# Basic_flex_IMU.net
KiCad netlist of a schematic drawn in Altium Designer
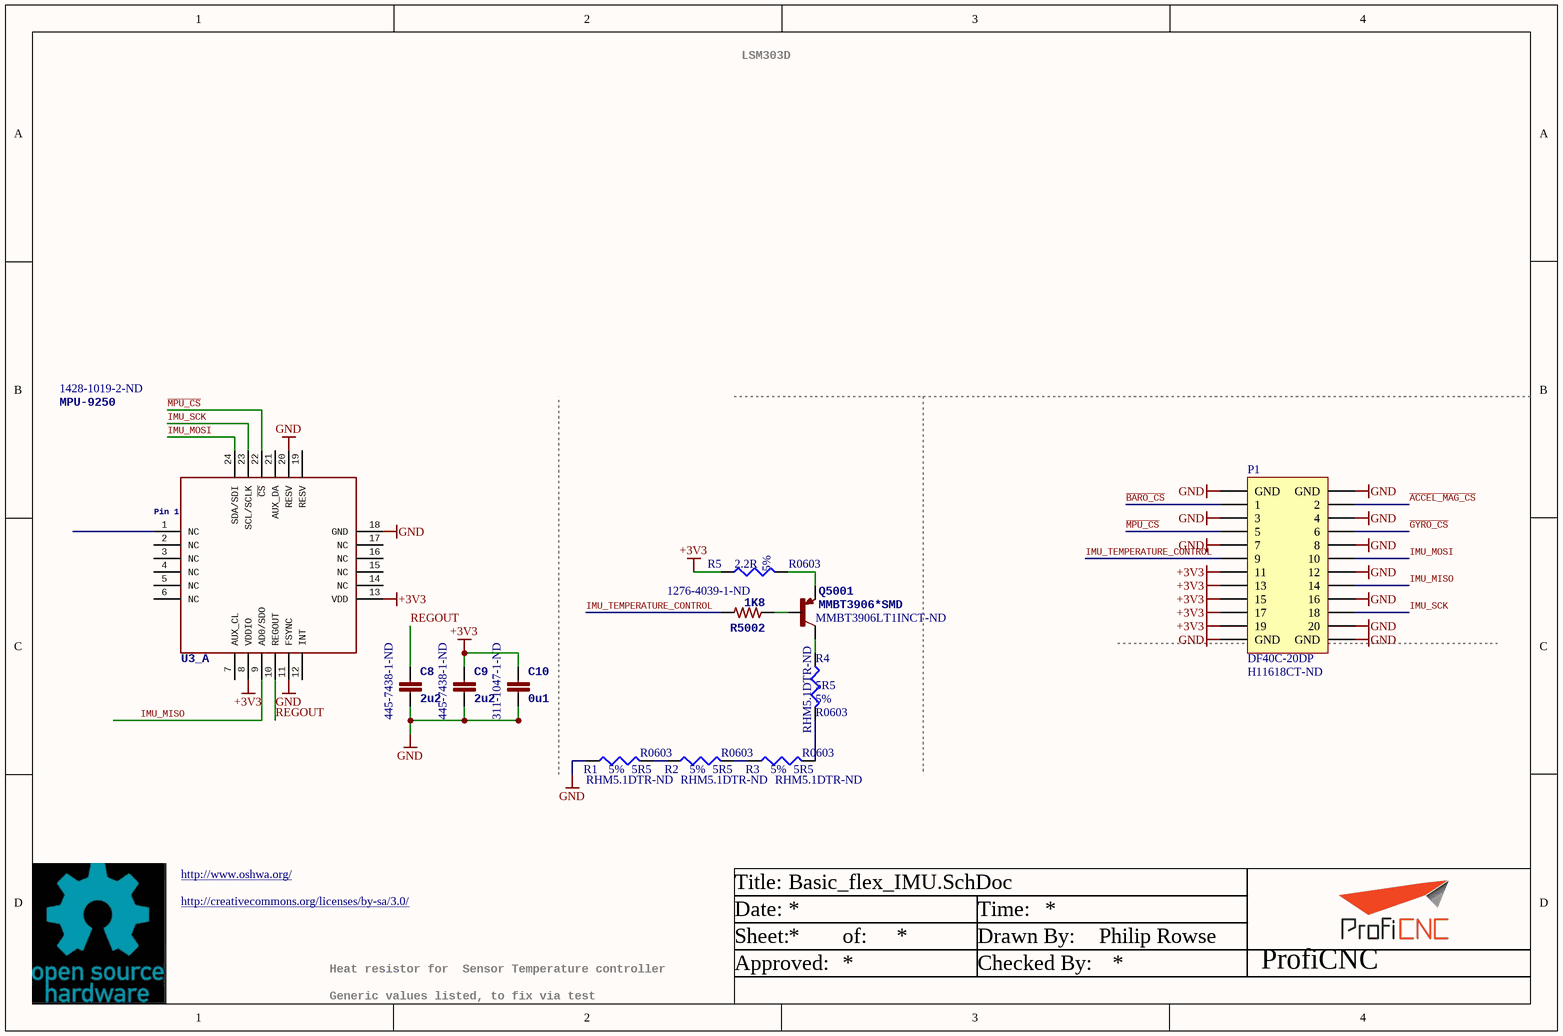
[diagram p0: Basic_flex_IMU.SchDoc]

(export (version "E")
  (design (tool "Eeschema 10.0.6"))
  (components
    (comp (ref "C8")
      (value "2u2")
      (footprint "0603-CAP")
      (description "Capacitor, 2.2uF, 16V, 10%, X6S, 0603, Ceramic")
      (fields
        (field (name "PARTNO") "C1608X6S1C225K080AC")
        (field (name "SUPPLIER PART NUMBER 1") "445-7438-1-ND")
        (field (name "3DR_PARTNO") "ECM0619")
      )
      (libsource (lib "lib_pixhawk") (part "CAPACITOR-0603"))
    )
    (comp (ref "C9")
      (value "2u2")
      (footprint "0603-CAP")
      (description "Capacitor, 2.2uF, 16V, 10%, X6S, 0603, Ceramic")
      (fields
        (field (name "PARTNO") "C1608X6S1C225K080AC")
        (field (name "SUPPLIER PART NUMBER 1") "445-7438-1-ND")
        (field (name "3DR_PARTNO") "ECM0619")
      )
      (libsource (lib "lib_pixhawk") (part "CAPACITOR-0603"))
    )
    (comp (ref "C10")
      (value "0u1")
      (footprint "0402-CAP")
      (description "Capacitor, 0.1uF, 16V, Y5V, 0402, Ceramic")
      (fields
        (field (name "PARTNO") "CC0402ZRY5V7BB104")
        (field (name "SUPPLIER PART NUMBER 1") "311-1047-1-ND")
        (field (name "3DR_PARTNO") "ECM0700")
      )
      (libsource (lib "lib_pixhawk") (part "CAPACITOR-0402"))
    )
    (comp (ref "P1")
      (value "DF40C-20DP")
      (footprint "DF40C-20-DP")
      (description "Connector, HDR, 20Pos, 0.4mm, SMD, GOLD")
      (fields
        (field (name "SUPPLIER PART NUMBER 1") "H11618CT-ND")
        (field (name "3DR_PARTNO") "ECM0510")
        (field (name "PUBLISHER") "Altium Limited")
      )
      (libsource (lib "pixhawk2") (part "DF40C-20DP"))
    )
    (comp (ref "Q5001")
      (value "MMBT3906*SMD")
      (footprint "SOT23-BEC")
      (description "TRANSISTOR SWITCHING PNP SOT-23")
      (fields
        (field (name "SUPPLIER PART NUMBER 1") "MMBT3906LT1INCT-ND")
        (field (name "3DR_PARTNO") "ECM0833")
        (field (name "PARTNO") "MMBT 3906 LT1")
      )
      (libsource (lib "transistor-pnp") (part "MMBT3906*SMD"))
    )
    (comp (ref "R1")
      (value "5R5")
      (footprint "R0603")
      (description "RES SMD 5.1 OHM 5% 1/4W 0603")
      (fields
        (field (name "TOLERANCE") "5%")
        (field (name "SUPPLIER PART NUMBER 1") "RHM5.1DTR-ND")
        (field (name "Comment") "Resistor")
      )
      (libsource (lib "3DR") (part "Resistor"))
    )
    (comp (ref "R2")
      (value "5R5")
      (footprint "R0603")
      (description "RES SMD 5.1 OHM 5% 1/4W 0603")
      (fields
        (field (name "TOLERANCE") "5%")
        (field (name "SUPPLIER PART NUMBER 1") "RHM5.1DTR-ND")
        (field (name "Comment") "Resistor")
      )
      (libsource (lib "3DR") (part "Resistor"))
    )
    (comp (ref "R3")
      (value "5R5")
      (footprint "R0603")
      (description "RES SMD 5.1 OHM 5% 1/4W 0603")
      (fields
        (field (name "TOLERANCE") "5%")
        (field (name "SUPPLIER PART NUMBER 1") "RHM5.1DTR-ND")
        (field (name "Comment") "Resistor")
      )
      (libsource (lib "3DR") (part "Resistor"))
    )
    (comp (ref "R4")
      (value "5R5")
      (footprint "R0603")
      (description "RES SMD 5.1 OHM 5% 1/4W 0603")
      (fields
        (field (name "TOLERANCE") "5%")
        (field (name "SUPPLIER PART NUMBER 1") "RHM5.1DTR-ND")
        (field (name "Comment") "Resistor")
      )
      (libsource (lib "3DR") (part "Resistor"))
    )
    (comp (ref "R5")
      (value "2.2R")
      (footprint "R0603")
      (description "RES SMD 5.1 OHM 5% 1/4W 0603")
      (fields (field (name "TOLERANCE") "5%") (field (name "Comment") "Resistor"))
      (libsource (lib "3DR") (part "Resistor"))
    )
    (comp (ref "R5002")
      (value "1K8")
      (footprint "0402-RES")
      (description "RES 1.8K OHM 1/16W 1% 0402")
      (fields
        (field (name "PARTNO") "RC1005F182CS")
        (field (name "SUPPLIER PART NUMBER 1") "1276-4039-1-ND")
        (field (name "3DR_PARTNO") "ECM0807")
      )
      (libsource (lib "pixhawk2") (part "RESISTOR0402-RES"))
    )
    (comp (ref "U3_A")
      (value "MPU-9250")
      (footprint "MPU-9250")
      (fields (field (name "PIN 1") "Pin 1") (field (name "SUPPLIER PART NUMBER 1") "1428-1019-2-ND"))
      (libsource (lib "pixhawk2") (part "MPU-6500"))
    )
  )
  (nets
    (net (code "1") (name "+3V3") (class "Default")
      (node (ref "C10") (pin "P$1") (pinfunction "1_P$1") (pintype "passive"))
      (node (ref "C9") (pin "P$1") (pinfunction "1_P$1") (pintype "passive"))
      (node (ref "P1") (pin "11") (pinfunction "11_11") (pintype "passive"))
      (node (ref "P1") (pin "13") (pinfunction "13_13") (pintype "passive"))
      (node (ref "P1") (pin "15") (pinfunction "15_15") (pintype "passive"))
      (node (ref "P1") (pin "17") (pinfunction "17_17") (pintype "passive"))
      (node (ref "P1") (pin "19") (pinfunction "19_19") (pintype "passive"))
      (node (ref "R5") (pin "1") (pinfunction "1_1") (pintype "passive"))
      (node (ref "U3_A") (pin "13") (pinfunction "VDD_13") (pintype "passive"))
      (node (ref "U3_A") (pin "8") (pinfunction "VDDIO_8") (pintype "passive"))
    )
    (net (code "2") (name "/IMU_MISO") (class "Default")
      (node (ref "P1") (pin "14") (pinfunction "14_14") (pintype "passive"))
      (node (ref "U3_A") (pin "9") (pinfunction "AD0/SDO_9") (pintype "passive"))
    )
    (net (code "3") (name "/IMU_MOSI") (class "Default")
      (node (ref "P1") (pin "10") (pinfunction "10_10") (pintype "passive"))
      (node (ref "U3_A") (pin "24") (pinfunction "SDA/SDI_24") (pintype "passive"))
    )
    (net (code "4") (name "/IMU_SCK") (class "Default")
      (node (ref "P1") (pin "18") (pinfunction "18_18") (pintype "passive"))
      (node (ref "U3_A") (pin "23") (pinfunction "SCL/SCLK_23") (pintype "passive"))
    )
    (net (code "5") (name "/IMU_TEMPERATURE_CONTROL") (class "Default")
      (node (ref "P1") (pin "9") (pinfunction "9_9") (pintype "passive"))
      (node (ref "R5002") (pin "P$2") (pinfunction "2_P$2") (pintype "passive"))
    )
    (net (code "6") (name "/REGOUT") (class "Default")
      (node (ref "C8") (pin "P$1") (pinfunction "1_P$1") (pintype "passive"))
      (node (ref "U3_A") (pin "10") (pinfunction "REGOUT_10") (pintype "passive"))
    )
    (net (code "7") (name "/~{ACCEL_MAG_CS}") (class "Default")
      (node (ref "P1") (pin "2") (pinfunction "2_2") (pintype "passive"))
    )
    (net (code "8") (name "/~{BARO_CS}") (class "Default")
      (node (ref "P1") (pin "1") (pinfunction "1_1") (pintype "passive"))
    )
    (net (code "9") (name "/~{GYRO_CS}") (class "Default")
      (node (ref "P1") (pin "6") (pinfunction "6_6") (pintype "passive"))
    )
    (net (code "10") (name "/~{MPU_CS}") (class "Default")
      (node (ref "P1") (pin "5") (pinfunction "5_5") (pintype "passive"))
      (node (ref "U3_A") (pin "22") (pinfunction "~{CS}_22") (pintype "passive"))
    )
    (net (code "11") (name "GND") (class "Default")
      (node (ref "C10") (pin "P$2") (pinfunction "2_P$2") (pintype "passive"))
      (node (ref "C8") (pin "P$2") (pinfunction "2_P$2") (pintype "passive"))
      (node (ref "C9") (pin "P$2") (pinfunction "2_P$2") (pintype "passive"))
      (node (ref "P1") (pin "12") (pinfunction "12_12") (pintype "passive"))
      (node (ref "P1") (pin "16") (pinfunction "16_16") (pintype "passive"))
      (node (ref "P1") (pin "20") (pinfunction "20_20") (pintype "passive"))
      (node (ref "P1") (pin "21") (pinfunction "GND_21") (pintype "passive"))
      (node (ref "P1") (pin "22") (pinfunction "GND_22") (pintype "passive"))
      (node (ref "P1") (pin "23") (pinfunction "GND_23") (pintype "passive"))
      (node (ref "P1") (pin "24") (pinfunction "GND_24") (pintype "passive"))
      (node (ref "P1") (pin "3") (pinfunction "3_3") (pintype "passive"))
      (node (ref "P1") (pin "4") (pinfunction "4_4") (pintype "passive"))
      (node (ref "P1") (pin "7") (pinfunction "7_7") (pintype "passive"))
      (node (ref "P1") (pin "8") (pinfunction "8_8") (pintype "passive"))
      (node (ref "R1") (pin "1") (pinfunction "1_1") (pintype "passive"))
      (node (ref "U3_A") (pin "11") (pinfunction "FSYNC_11") (pintype "passive"))
      (node (ref "U3_A") (pin "18") (pinfunction "GND_18") (pintype "passive"))
      (node (ref "U3_A") (pin "20") (pinfunction "RESV_20") (pintype "passive"))
    )
    (net (code "12") (name "Net-(Q5001-PadC)") (class "Default")
      (node (ref "Q5001") (pin "C") (pinfunction "C_C") (pintype "passive"))
      (node (ref "R4") (pin "1") (pinfunction "1_1") (pintype "passive"))
    )
    (net (code "13") (name "Net-(Q5001-PadE)") (class "Default")
      (node (ref "Q5001") (pin "E") (pinfunction "E_E") (pintype "passive"))
      (node (ref "R5") (pin "2") (pinfunction "2_2") (pintype "passive"))
    )
    (net (code "14") (name "Net-(R1-Pad2)") (class "Default")
      (node (ref "R1") (pin "2") (pinfunction "2_2") (pintype "passive"))
      (node (ref "R2") (pin "1") (pinfunction "1_1") (pintype "passive"))
    )
    (net (code "15") (name "Net-(R2-Pad2)") (class "Default")
      (node (ref "R2") (pin "2") (pinfunction "2_2") (pintype "passive"))
      (node (ref "R3") (pin "1") (pinfunction "1_1") (pintype "passive"))
    )
    (net (code "16") (name "Net-(R3-Pad2)") (class "Default")
      (node (ref "R3") (pin "2") (pinfunction "2_2") (pintype "passive"))
      (node (ref "R4") (pin "2") (pinfunction "2_2") (pintype "passive"))
    )
    (net (code "17") (name "Net-(R5002-1)") (class "Default")
      (node (ref "Q5001") (pin "B") (pinfunction "B_B") (pintype "passive"))
      (node (ref "R5002") (pin "P$1") (pinfunction "1_P$1") (pintype "passive"))
    )
    (net (code "18") (name "unconnected-(U3_A-AUX_CL-Pad7)") (class "Default")
      (node (ref "U3_A") (pin "7") (pinfunction "AUX_CL_7") (pintype "passive"))
    )
    (net (code "19") (name "unconnected-(U3_A-AUX_DA-Pad21)") (class "Default")
      (node (ref "U3_A") (pin "21") (pinfunction "AUX_DA_21") (pintype "passive"))
    )
    (net (code "20") (name "unconnected-(U3_A-INT-Pad12)") (class "Default")
      (node (ref "U3_A") (pin "12") (pinfunction "INT_12") (pintype "passive"))
    )
    (net (code "21") (name "unconnected-(U3_A-NC-Pad1)") (class "Default")
      (node (ref "U3_A") (pin "1") (pinfunction "NC_1") (pintype "passive"))
    )
    (net (code "22") (name "unconnected-(U3_A-NC-Pad2)") (class "Default")
      (node (ref "U3_A") (pin "2") (pinfunction "NC_2") (pintype "passive"))
    )
    (net (code "23") (name "unconnected-(U3_A-NC-Pad3)") (class "Default")
      (node (ref "U3_A") (pin "3") (pinfunction "NC_3") (pintype "passive"))
    )
    (net (code "24") (name "unconnected-(U3_A-NC-Pad4)") (class "Default")
      (node (ref "U3_A") (pin "4") (pinfunction "NC_4") (pintype "passive"))
    )
    (net (code "25") (name "unconnected-(U3_A-NC-Pad5)") (class "Default")
      (node (ref "U3_A") (pin "5") (pinfunction "NC_5") (pintype "passive"))
    )
    (net (code "26") (name "unconnected-(U3_A-NC-Pad6)") (class "Default")
      (node (ref "U3_A") (pin "6") (pinfunction "NC_6") (pintype "passive"))
    )
    (net (code "27") (name "unconnected-(U3_A-NC-Pad14)") (class "Default")
      (node (ref "U3_A") (pin "14") (pinfunction "NC_14") (pintype "passive"))
    )
    (net (code "28") (name "unconnected-(U3_A-NC-Pad15)") (class "Default")
      (node (ref "U3_A") (pin "15") (pinfunction "NC_15") (pintype "passive"))
    )
    (net (code "29") (name "unconnected-(U3_A-NC-Pad16)") (class "Default")
      (node (ref "U3_A") (pin "16") (pinfunction "NC_16") (pintype "passive"))
    )
    (net (code "30") (name "unconnected-(U3_A-NC-Pad17)") (class "Default")
      (node (ref "U3_A") (pin "17") (pinfunction "NC_17") (pintype "passive"))
    )
    (net (code "31") (name "unconnected-(U3_A-RESV-Pad19)") (class "Default")
      (node (ref "U3_A") (pin "19") (pinfunction "RESV_19") (pintype "passive"))
    )
  )
)
